# PCB_mezzanine_analog_template.net
KiCad netlist of a schematic drawn in Altium Designer
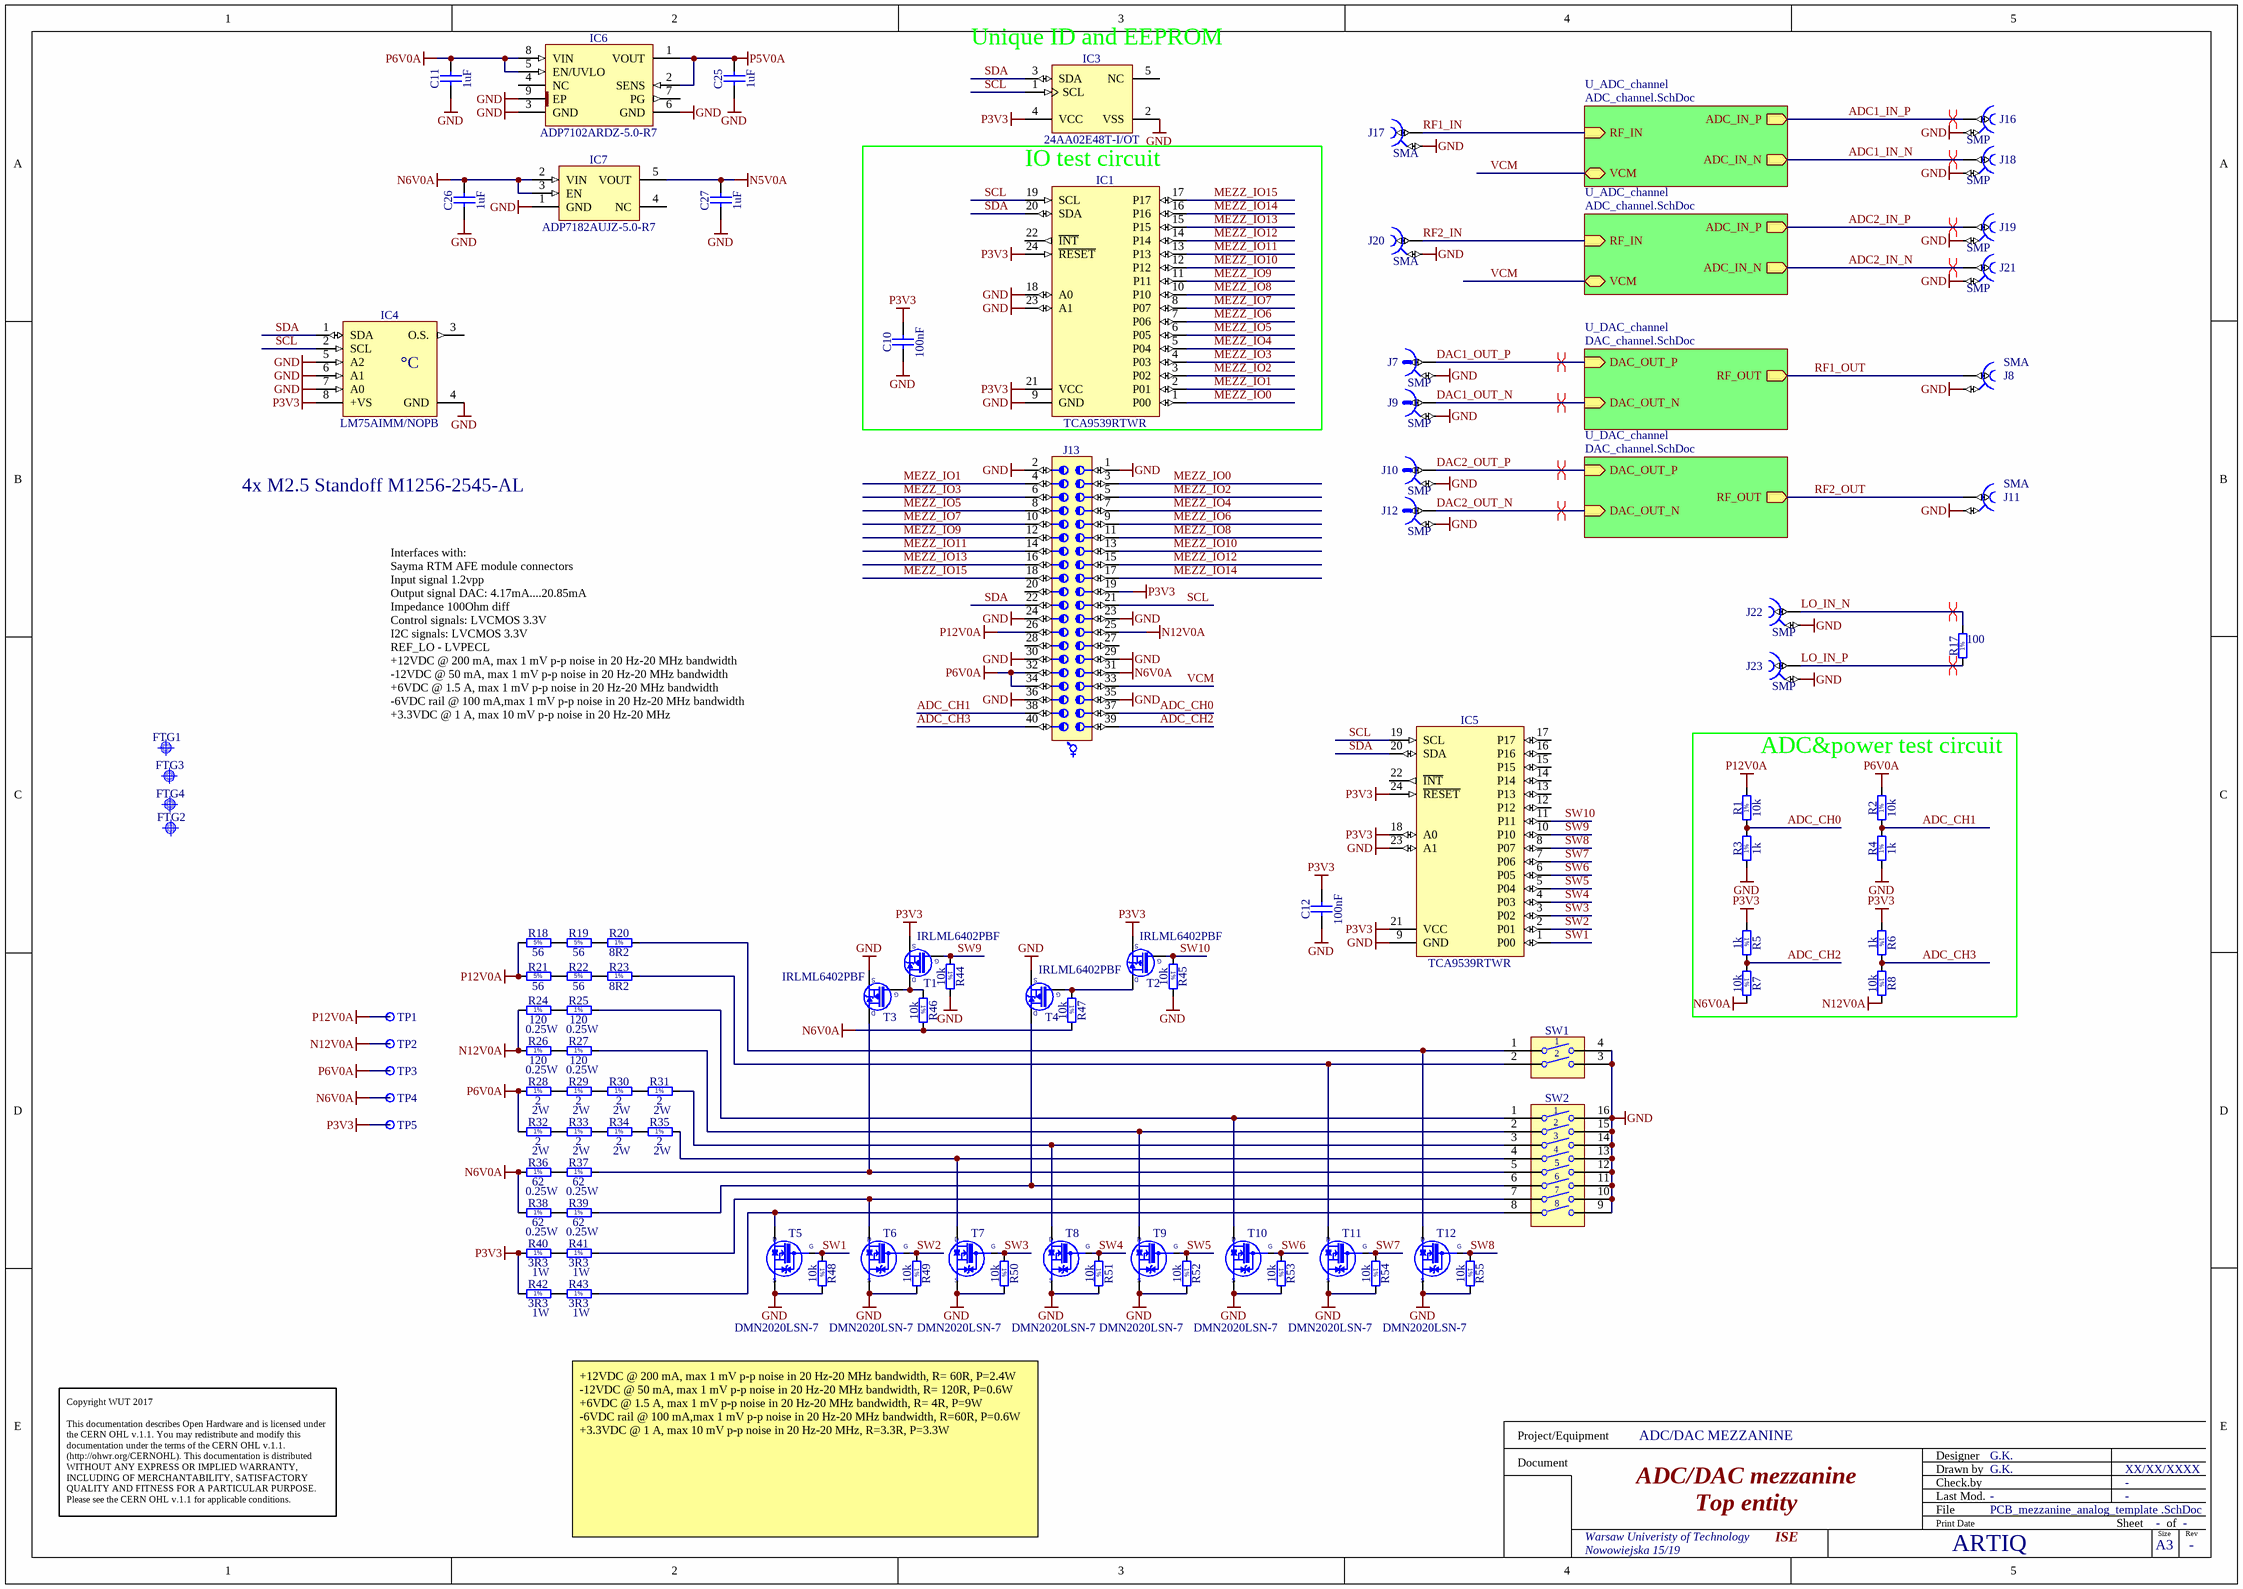
[diagram p0: PCB_mezzanine_analog_template .SchDoc]

(export (version "E")
  (design (tool "Eeschema 10.0.6"))
  (components
    (comp (ref "C10")
      (value "100nF")
      (footprint "CAPC1005X55N")
      (description "Non-polarised capacitor")
      (fields
        (field (name "PART NUMBER") "CC0402_100NF_16V_10%_X5R")
        (field (name "VOLTAGE") "16V")
        (field (name "AUTHOR") "CERN DEM JLC")
      )
      (libsource (lib "Capacitors") (part "Capacitor - non polarized"))
    )
    (comp (ref "C11")
      (value "1uF")
      (footprint "CAPC2012X140N")
      (description "Non-polarised capacitor")
      (fields
        (field (name "PART NUMBER") "CC0805_1UF_35V_20%_X7R")
        (field (name "VOLTAGE") "35V")
        (field (name "AUTHOR") "CERN DEM JLC")
      )
      (libsource (lib "Capacitors") (part "Capacitor - non polarized"))
    )
    (comp (ref "C12")
      (value "100nF")
      (footprint "CAPC1005X55N")
      (description "Non-polarised capacitor")
      (fields
        (field (name "PART NUMBER") "CC0402_100NF_16V_10%_X5R")
        (field (name "VOLTAGE") "16V")
        (field (name "AUTHOR") "CERN DEM JLC")
      )
      (libsource (lib "Capacitors") (part "Capacitor - non polarized"))
    )
    (comp (ref "C25")
      (value "1uF")
      (footprint "CAPC2012X140N")
      (description "Non-polarised capacitor")
      (fields
        (field (name "PART NUMBER") "CC0805_1UF_35V_20%_X7R")
        (field (name "VOLTAGE") "35V")
        (field (name "AUTHOR") "CERN DEM JLC")
      )
      (libsource (lib "Capacitors") (part "Capacitor - non polarized"))
    )
    (comp (ref "C26")
      (value "1uF")
      (footprint "CAPC2012X140N")
      (description "Non-polarised capacitor")
      (fields
        (field (name "PART NUMBER") "CC0805_1UF_35V_20%_X7R")
        (field (name "VOLTAGE") "35V")
        (field (name "AUTHOR") "CERN DEM JLC")
      )
      (libsource (lib "Capacitors") (part "Capacitor - non polarized"))
    )
    (comp (ref "C27")
      (value "1uF")
      (footprint "CAPC2012X140N")
      (description "Non-polarised capacitor")
      (fields
        (field (name "PART NUMBER") "CC0805_1UF_35V_20%_X7R")
        (field (name "VOLTAGE") "35V")
        (field (name "AUTHOR") "CERN DEM JLC")
      )
      (libsource (lib "Capacitors") (part "Capacitor - non polarized"))
    )
    (comp (ref "FTG1")
      (value "Use only in PCB")
      (footprint "FIDUCIAL_TOP_C100-200")
      (description "Fiducial Target")
      (fields (field (name "PART NUMBER") "FIDUCIAL_TARGET_C100-200") (field (name "AUTHOR") "CERN DEM JLC"))
      (libsource (lib "Eletro-mechanical") (part "Fiducial Target"))
    )
    (comp (ref "FTG2")
      (value "Use only in PCB")
      (footprint "FIDUCIAL_TOP_S100-200")
      (description "Fiducial Target")
      (fields (field (name "PART NUMBER") "FIDUCIAL_TARGET_S100-200") (field (name "AUTHOR") "CERN DEM JLC"))
      (libsource (lib "Eletro-mechanical") (part "Fiducial Target"))
    )
    (comp (ref "FTG3")
      (value "Use only in PCB")
      (footprint "FIDUCIAL_TOP_S100-200")
      (description "Fiducial Target")
      (fields (field (name "PART NUMBER") "FIDUCIAL_TARGET_S100-200") (field (name "AUTHOR") "CERN DEM JLC"))
      (libsource (lib "Eletro-mechanical") (part "Fiducial Target"))
    )
    (comp (ref "FTG4")
      (value "Use only in PCB")
      (footprint "FIDUCIAL_TOP_S200-400")
      (description "Fiducial Target")
      (fields (field (name "PART NUMBER") "FIDUCIAL_TARGET_S200-400") (field (name "AUTHOR") "CERN DEM JLC"))
      (libsource (lib "Eletro-mechanical") (part "Fiducial Target"))
    )
    (comp (ref "IC1")
      (value "TCA9539RTWR")
      (footprint "QFN50P400X400X80-25N-S255")
      (description "Low-Voltage 16-Bit I2C and SMBus I/O Expander")
      (fields (field (name "MANUFACTURER") "TEXAS INSTRUMENTS") (field (name "AUTHOR") "CERN DEM MR"))
      (libsource (lib "ICs And Semiconductors") (part "TCA9539RTWR"))
    )
    (comp (ref "IC3")
      (value "24AA02E48T-I/OT")
      (footprint "SOT95P280X145-5N")
      (description "1.7V-5.5V, 2K I2C Serial EEPROM With EUI-48 Node Identity")
      (fields (field (name "MANUFACTURER") "MICROCHIP TECHNOLOGY") (field (name "AUTHOR") "CERN DEM MR"))
      (libsource (lib "ICs And Semiconductors") (part "24AA02E48T-I/OT"))
    )
    (comp (ref "IC4")
      (value "LM75AIMM/NOPB")
      (footprint "SOP65P490X109-8N")
      (description "Digital Temperature Sensor and Thermal Watchdog with Two-Wire Interface")
      (fields (field (name "MANUFACTURER") "TEXAS INSTRUMENTS") (field (name "AUTHOR") "CERN DEM JLC"))
      (libsource (lib "ICs And Semiconductors") (part "LM75"))
    )
    (comp (ref "IC5")
      (value "TCA9539RTWR")
      (footprint "QFN50P400X400X80-25N-S255")
      (description "Low-Voltage 16-Bit I2C and SMBus I/O Expander")
      (fields (field (name "MANUFACTURER") "TEXAS INSTRUMENTS") (field (name "AUTHOR") "CERN DEM MR"))
      (libsource (lib "ICs And Semiconductors") (part "TCA9539RTWR"))
    )
    (comp (ref "IC6")
      (value "ADP7102ARDZ-5.0-R7")
      (footprint "SOIC127P600X175-9N-R241X309")
      (description "300 mA, Low Noise, CMOS LDO Linear Regulator")
      (fields (field (name "MANUFACTURER") "ANALOG DEVICES") (field (name "AUTHOR") "CERN DEM JLC"))
      (libsource (lib "ICs And Semiconductors") (part "ADP7102ARDZ-X.X-R7"))
    )
    (comp (ref "IC7")
      (value "ADP7182AUJZ-5.0-R7")
      (footprint "SOT95P280X90-5N")
      (description "–5V, 200 mA, Low Noise, Linear Regulator")
      (fields (field (name "MANUFACTURER") "ANALOG DEVICES") (field (name "AUTHOR") "CERN DEM JLC"))
      (libsource (lib "ICs And Semiconductors") (part "ADP7182AUJZ-X.X-R7"))
    )
    (comp (ref "J7")
      (value "SMP")
      (footprint "MOLEX_85305-0232")
      (fields
        (field (name "PART NUMBER") "MOLEX_85305-0232")
        (field (name "MANUFACTURER") "MOLEX")
        (field (name "MANUFACTURER PART NUMBER") "85305-0232")
        (field (name "AUTHOR") "CERN DEM JMW")
      )
      (libsource (lib "Connectors") (part "Coax_1Male_1Shield"))
    )
    (comp (ref "J8")
      (value "SMA")
      (footprint "TELEGARTNER_J01151A0451")
      (fields
        (field (name "PART NUMBER") "TELEGARTNER_J01151A0451")
        (field (name "MANUFACTURER") "TELEGARTNER")
        (field (name "MANUFACTURER PART NUMBER") "J01151A0451")
        (field (name "AUTHOR") "CERN DEM JLC")
      )
      (libsource (lib "") (part "Coax_1Female_1Shield_1"))
    )
    (comp (ref "J9")
      (value "SMP")
      (footprint "MOLEX_85305-0232")
      (fields
        (field (name "PART NUMBER") "MOLEX_85305-0232")
        (field (name "MANUFACTURER") "MOLEX")
        (field (name "MANUFACTURER PART NUMBER") "85305-0232")
        (field (name "AUTHOR") "CERN DEM JMW")
      )
      (libsource (lib "Connectors") (part "Coax_1Male_1Shield"))
    )
    (comp (ref "J10")
      (value "SMP")
      (footprint "MOLEX_85305-0232")
      (fields
        (field (name "PART NUMBER") "MOLEX_85305-0232")
        (field (name "MANUFACTURER") "MOLEX")
        (field (name "MANUFACTURER PART NUMBER") "85305-0232")
        (field (name "AUTHOR") "CERN DEM JMW")
      )
      (libsource (lib "Connectors") (part "Coax_1Male_1Shield"))
    )
    (comp (ref "J11")
      (value "SMA")
      (footprint "TELEGARTNER_J01151A0451")
      (fields
        (field (name "PART NUMBER") "TELEGARTNER_J01151A0451")
        (field (name "MANUFACTURER") "TELEGARTNER")
        (field (name "MANUFACTURER PART NUMBER") "J01151A0451")
        (field (name "AUTHOR") "CERN DEM JLC")
      )
      (libsource (lib "") (part "Coax_1Female_1Shield_1"))
    )
    (comp (ref "J12")
      (value "SMP")
      (footprint "MOLEX_85305-0232")
      (fields
        (field (name "PART NUMBER") "MOLEX_85305-0232")
        (field (name "MANUFACTURER") "MOLEX")
        (field (name "MANUFACTURER PART NUMBER") "85305-0232")
        (field (name "AUTHOR") "CERN DEM JMW")
      )
      (libsource (lib "Connectors") (part "Coax_1Male_1Shield"))
    )
    (comp (ref "J13")
      (value "~")
      (footprint "SAMTEC_LSS-120-02-L-DV-A")
      (fields
        (field (name "PART NUMBER") "SAMTEC_LSS-120-02-L-DV-A")
        (field (name "MANUFACTURER") "SAMTEC")
        (field (name "MANUFACTURER PART NUMBER") "LSS-120-02-L-DV-A")
        (field (name "AUTHOR") "CERN DEM JMW")
      )
      (libsource (lib "LIBRARY_SCH") (part "CON_SAMTEC_LSS-120-02-L-DV-A"))
    )
    (comp (ref "J16")
      (value "SMP")
      (footprint "AMPHENOL_SMP-MSLD-PCT-10")
      (fields
        (field (name "PART NUMBER") "AMPHENOL_SMP-MSLD-PCT-10")
        (field (name "MANUFACTURER") "AMPHENOL")
        (field (name "MANUFACTURER PART NUMBER") "SMP-MSLD-PCT-10")
        (field (name "AUTHOR") "CERN DEM JLC")
      )
      (libsource (lib "") (part "Coax_1Female_1Shield_1"))
    )
    (comp (ref "J17")
      (value "SMA")
      (footprint "TELEGARTNER_J01151A0921")
      (fields
        (field (name "PART NUMBER") "TELEGARTNER_J01151A0921")
        (field (name "MANUFACTURER") "TELEGARTNER")
        (field (name "MANUFACTURER PART NUMBER") "J01151A0921")
        (field (name "AUTHOR") "CERN DEM JLC")
      )
      (libsource (lib "Connectors") (part "Coax_1Female_1Shield"))
    )
    (comp (ref "J18")
      (value "SMP")
      (footprint "AMPHENOL_SMP-MSLD-PCT-10")
      (fields
        (field (name "PART NUMBER") "AMPHENOL_SMP-MSLD-PCT-10")
        (field (name "MANUFACTURER") "AMPHENOL")
        (field (name "MANUFACTURER PART NUMBER") "SMP-MSLD-PCT-10")
        (field (name "AUTHOR") "CERN DEM JLC")
      )
      (libsource (lib "") (part "Coax_1Female_1Shield_1"))
    )
    (comp (ref "J19")
      (value "SMP")
      (footprint "AMPHENOL_SMP-MSLD-PCT-10")
      (fields
        (field (name "PART NUMBER") "AMPHENOL_SMP-MSLD-PCT-10")
        (field (name "MANUFACTURER") "AMPHENOL")
        (field (name "MANUFACTURER PART NUMBER") "SMP-MSLD-PCT-10")
        (field (name "AUTHOR") "CERN DEM JLC")
      )
      (libsource (lib "") (part "Coax_1Female_1Shield_1"))
    )
    (comp (ref "J20")
      (value "SMA")
      (footprint "TELEGARTNER_J01151A0921")
      (fields
        (field (name "PART NUMBER") "TELEGARTNER_J01151A0921")
        (field (name "MANUFACTURER") "TELEGARTNER")
        (field (name "MANUFACTURER PART NUMBER") "J01151A0921")
        (field (name "AUTHOR") "CERN DEM JLC")
      )
      (libsource (lib "Connectors") (part "Coax_1Female_1Shield"))
    )
    (comp (ref "J21")
      (value "SMP")
      (footprint "AMPHENOL_SMP-MSLD-PCT-10")
      (fields
        (field (name "PART NUMBER") "AMPHENOL_SMP-MSLD-PCT-10")
        (field (name "MANUFACTURER") "AMPHENOL")
        (field (name "MANUFACTURER PART NUMBER") "SMP-MSLD-PCT-10")
        (field (name "AUTHOR") "CERN DEM JLC")
      )
      (libsource (lib "") (part "Coax_1Female_1Shield_1"))
    )
    (comp (ref "J22")
      (value "SMP")
      (footprint "AMPHENOL_SMP-MSLD-PCT-10")
      (fields
        (field (name "PART NUMBER") "AMPHENOL_SMP-MSLD-PCT-10")
        (field (name "MANUFACTURER") "AMPHENOL")
        (field (name "MANUFACTURER PART NUMBER") "SMP-MSLD-PCT-10")
        (field (name "AUTHOR") "CERN DEM JLC")
      )
      (libsource (lib "Connectors") (part "Coax_1Female_1Shield"))
    )
    (comp (ref "J23")
      (value "SMP")
      (footprint "AMPHENOL_SMP-MSLD-PCT-10")
      (fields
        (field (name "PART NUMBER") "AMPHENOL_SMP-MSLD-PCT-10")
        (field (name "MANUFACTURER") "AMPHENOL")
        (field (name "MANUFACTURER PART NUMBER") "SMP-MSLD-PCT-10")
        (field (name "AUTHOR") "CERN DEM JLC")
      )
      (libsource (lib "Connectors") (part "Coax_1Female_1Shield"))
    )
    (comp (ref "R1")
      (value "10k")
      (footprint "RESC1005X40N")
      (description "Resistor - 1%")
      (fields
        (field (name "PART NUMBER") "R0402_10K_1%_0.0625W_100PPM")
        (field (name "POWER") "0.0625W")
        (field (name "AUTHOR") "CERN DEM JLC")
      )
      (libsource (lib "Resistors") (part "Resistor - 1%"))
    )
    (comp (ref "R2")
      (value "10k")
      (footprint "RESC1005X40N")
      (description "Resistor - 1%")
      (fields
        (field (name "PART NUMBER") "R0402_10K_1%_0.0625W_100PPM")
        (field (name "POWER") "0.0625W")
        (field (name "AUTHOR") "CERN DEM JLC")
      )
      (libsource (lib "Resistors") (part "Resistor - 1%"))
    )
    (comp (ref "R3")
      (value "1k")
      (footprint "RESC1005X40N")
      (description "Resistor - 1%")
      (fields
        (field (name "PART NUMBER") "R0402_1K_1%_0.0625W_100PPM")
        (field (name "POWER") "0.0625W")
        (field (name "AUTHOR") "CERN DEM JLC")
      )
      (libsource (lib "Resistors") (part "Resistor - 1%"))
    )
    (comp (ref "R4")
      (value "1k")
      (footprint "RESC1005X40N")
      (description "Resistor - 1%")
      (fields
        (field (name "PART NUMBER") "R0402_1K_1%_0.0625W_100PPM")
        (field (name "POWER") "0.0625W")
        (field (name "AUTHOR") "CERN DEM JLC")
      )
      (libsource (lib "Resistors") (part "Resistor - 1%"))
    )
    (comp (ref "R5")
      (value "1k")
      (footprint "RESC1005X40N")
      (description "Resistor - 1%")
      (fields
        (field (name "PART NUMBER") "R0402_1K_1%_0.0625W_100PPM")
        (field (name "POWER") "0.0625W")
        (field (name "AUTHOR") "CERN DEM JLC")
      )
      (libsource (lib "Resistors") (part "Resistor - 1%"))
    )
    (comp (ref "R6")
      (value "1k")
      (footprint "RESC1005X40N")
      (description "Resistor - 1%")
      (fields
        (field (name "PART NUMBER") "R0402_1K_1%_0.0625W_100PPM")
        (field (name "POWER") "0.0625W")
        (field (name "AUTHOR") "CERN DEM JLC")
      )
      (libsource (lib "Resistors") (part "Resistor - 1%"))
    )
    (comp (ref "R7")
      (value "10k")
      (footprint "RESC1005X40N")
      (description "Resistor - 1%")
      (fields
        (field (name "PART NUMBER") "R0402_10K_1%_0.0625W_100PPM")
        (field (name "POWER") "0.0625W")
        (field (name "AUTHOR") "CERN DEM JLC")
      )
      (libsource (lib "Resistors") (part "Resistor - 1%"))
    )
    (comp (ref "R8")
      (value "10k")
      (footprint "RESC1005X40N")
      (description "Resistor - 1%")
      (fields
        (field (name "PART NUMBER") "R0402_10K_1%_0.0625W_100PPM")
        (field (name "POWER") "0.0625W")
        (field (name "AUTHOR") "CERN DEM JLC")
      )
      (libsource (lib "Resistors") (part "Resistor - 1%"))
    )
    (comp (ref "R17")
      (value "100")
      (footprint "RESC1005X40N")
      (description "Resistor - 1%")
      (fields
        (field (name "PART NUMBER") "R0402_100R_1%_0.0625W_100PPM")
        (field (name "POWER") "0.0625W")
        (field (name "AUTHOR") "CERN DEM JLC")
      )
      (libsource (lib "Resistors") (part "Resistor - 1%"))
    )
    (comp (ref "R18")
      (value "56")
      (footprint "RESC6331X70N")
      (description "Resistor - 5%")
      (fields
        (field (name "PART NUMBER") "R2512_56R_5%_1W_200PPM")
        (field (name "POWER") "1W")
        (field (name "AUTHOR") "CERN DEM JLC")
      )
      (libsource (lib "Resistors") (part "Resistor - 5%"))
    )
    (comp (ref "R19")
      (value "56")
      (footprint "RESC6331X70N")
      (description "Resistor - 5%")
      (fields
        (field (name "PART NUMBER") "R2512_56R_5%_1W_200PPM")
        (field (name "POWER") "1W")
        (field (name "AUTHOR") "CERN DEM JLC")
      )
      (libsource (lib "Resistors") (part "Resistor - 5%"))
    )
    (comp (ref "R20")
      (value "8R2")
      (footprint "RESC3216X65N")
      (description "Resistor - 1%")
      (fields
        (field (name "PART NUMBER") "R1206_8R2_1%_0.25W_200PPM")
        (field (name "POWER") "0.25W")
        (field (name "AUTHOR") "CERN DEM JLC")
      )
      (libsource (lib "Resistors") (part "Resistor - 1%"))
    )
    (comp (ref "R21")
      (value "56")
      (footprint "RESC6331X70N")
      (description "Resistor - 5%")
      (fields
        (field (name "PART NUMBER") "R2512_56R_5%_1W_200PPM")
        (field (name "POWER") "1W")
        (field (name "AUTHOR") "CERN DEM JLC")
      )
      (libsource (lib "Resistors") (part "Resistor - 5%"))
    )
    (comp (ref "R22")
      (value "56")
      (footprint "RESC6331X70N")
      (description "Resistor - 5%")
      (fields
        (field (name "PART NUMBER") "R2512_56R_5%_1W_200PPM")
        (field (name "POWER") "1W")
        (field (name "AUTHOR") "CERN DEM JLC")
      )
      (libsource (lib "Resistors") (part "Resistor - 5%"))
    )
    (comp (ref "R23")
      (value "8R2")
      (footprint "RESC3216X65N")
      (description "Resistor - 1%")
      (fields
        (field (name "PART NUMBER") "R1206_8R2_1%_0.25W_200PPM")
        (field (name "POWER") "0.25W")
        (field (name "AUTHOR") "CERN DEM JLC")
      )
      (libsource (lib "Resistors") (part "Resistor - 1%"))
    )
    (comp (ref "R24")
      (value "120")
      (footprint "RESC3216X65N")
      (description "Resistor - 1%")
      (fields
        (field (name "PART NUMBER") "R1206_120R_1%_0.25W_100PPM")
        (field (name "POWER") "0.25W")
        (field (name "TOLERANCE") "±1%")
        (field (name "AUTHOR") "CERN DEM JLC")
      )
      (libsource (lib "Resistors") (part "Resistor - 1%"))
    )
    (comp (ref "R25")
      (value "120")
      (footprint "RESC3216X65N")
      (description "Resistor - 1%")
      (fields
        (field (name "PART NUMBER") "R1206_120R_1%_0.25W_100PPM")
        (field (name "POWER") "0.25W")
        (field (name "TOLERANCE") "±1%")
        (field (name "AUTHOR") "CERN DEM JLC")
      )
      (libsource (lib "Resistors") (part "Resistor - 1%"))
    )
    (comp (ref "R26")
      (value "120")
      (footprint "RESC3216X65N")
      (description "Resistor - 1%")
      (fields
        (field (name "PART NUMBER") "R1206_120R_1%_0.25W_100PPM")
        (field (name "POWER") "0.25W")
        (field (name "TOLERANCE") "±1%")
        (field (name "AUTHOR") "CERN DEM JLC")
      )
      (libsource (lib "Resistors") (part "Resistor - 1%"))
    )
    (comp (ref "R27")
      (value "120")
      (footprint "RESC3216X65N")
      (description "Resistor - 1%")
      (fields
        (field (name "PART NUMBER") "R1206_120R_1%_0.25W_100PPM")
        (field (name "POWER") "0.25W")
        (field (name "TOLERANCE") "±1%")
        (field (name "AUTHOR") "CERN DEM JLC")
      )
      (libsource (lib "Resistors") (part "Resistor - 1%"))
    )
    (comp (ref "R28")
      (value "2")
      (footprint "RESM11670X449N")
      (description "Resistor - 1%")
      (fields
        (field (name "PART NUMBER") "R4527_2R_1%_2W_50PPM")
        (field (name "POWER") "2W")
        (field (name "TOLERANCE") "±1%")
        (field (name "AUTHOR") "CERN DEM JLC")
      )
      (libsource (lib "Resistors") (part "Resistor - 1%"))
    )
    (comp (ref "R29")
      (value "2")
      (footprint "RESM11670X449N")
      (description "Resistor - 1%")
      (fields
        (field (name "PART NUMBER") "R4527_2R_1%_2W_50PPM")
        (field (name "POWER") "2W")
        (field (name "TOLERANCE") "±1%")
        (field (name "AUTHOR") "CERN DEM JLC")
      )
      (libsource (lib "Resistors") (part "Resistor - 1%"))
    )
    (comp (ref "R30")
      (value "2")
      (footprint "RESM11670X449N")
      (description "Resistor - 1%")
      (fields
        (field (name "PART NUMBER") "R4527_2R_1%_2W_50PPM")
        (field (name "POWER") "2W")
        (field (name "TOLERANCE") "±1%")
        (field (name "AUTHOR") "CERN DEM JLC")
      )
      (libsource (lib "Resistors") (part "Resistor - 1%"))
    )
    (comp (ref "R31")
      (value "2")
      (footprint "RESM11670X449N")
      (description "Resistor - 1%")
      (fields
        (field (name "PART NUMBER") "R4527_2R_1%_2W_50PPM")
        (field (name "POWER") "2W")
        (field (name "TOLERANCE") "±1%")
        (field (name "AUTHOR") "CERN DEM JLC")
      )
      (libsource (lib "Resistors") (part "Resistor - 1%"))
    )
    (comp (ref "R32")
      (value "2")
      (footprint "RESM11670X449N")
      (description "Resistor - 1%")
      (fields
        (field (name "PART NUMBER") "R4527_2R_1%_2W_50PPM")
        (field (name "POWER") "2W")
        (field (name "TOLERANCE") "±1%")
        (field (name "AUTHOR") "CERN DEM JLC")
      )
      (libsource (lib "Resistors") (part "Resistor - 1%"))
    )
    (comp (ref "R33")
      (value "2")
      (footprint "RESM11670X449N")
      (description "Resistor - 1%")
      (fields
        (field (name "PART NUMBER") "R4527_2R_1%_2W_50PPM")
        (field (name "POWER") "2W")
        (field (name "TOLERANCE") "±1%")
        (field (name "AUTHOR") "CERN DEM JLC")
      )
      (libsource (lib "Resistors") (part "Resistor - 1%"))
    )
    (comp (ref "R34")
      (value "2")
      (footprint "RESM11670X449N")
      (description "Resistor - 1%")
      (fields
        (field (name "PART NUMBER") "R4527_2R_1%_2W_50PPM")
        (field (name "POWER") "2W")
        (field (name "TOLERANCE") "±1%")
        (field (name "AUTHOR") "CERN DEM JLC")
      )
      (libsource (lib "Resistors") (part "Resistor - 1%"))
    )
    (comp (ref "R35")
      (value "2")
      (footprint "RESM11670X449N")
      (description "Resistor - 1%")
      (fields
        (field (name "PART NUMBER") "R4527_2R_1%_2W_50PPM")
        (field (name "POWER") "2W")
        (field (name "TOLERANCE") "±1%")
        (field (name "AUTHOR") "CERN DEM JLC")
      )
      (libsource (lib "Resistors") (part "Resistor - 1%"))
    )
    (comp (ref "R36")
      (value "62")
      (footprint "RESC3216X65N")
      (description "Resistor - 1%")
      (fields
        (field (name "PART NUMBER") "R1206_62R_1%_0.25W_100PPM")
        (field (name "POWER") "0.25W")
        (field (name "TOLERANCE") "±1%")
        (field (name "AUTHOR") "CERN DEM JLC")
      )
      (libsource (lib "Resistors") (part "Resistor - 1%"))
    )
    (comp (ref "R37")
      (value "62")
      (footprint "RESC3216X65N")
      (description "Resistor - 1%")
      (fields
        (field (name "PART NUMBER") "R1206_62R_1%_0.25W_100PPM")
        (field (name "POWER") "0.25W")
        (field (name "TOLERANCE") "±1%")
        (field (name "AUTHOR") "CERN DEM JLC")
      )
      (libsource (lib "Resistors") (part "Resistor - 1%"))
    )
    (comp (ref "R38")
      (value "62")
      (footprint "RESC3216X65N")
      (description "Resistor - 1%")
      (fields
        (field (name "PART NUMBER") "R1206_62R_1%_0.25W_100PPM")
        (field (name "POWER") "0.25W")
        (field (name "TOLERANCE") "±1%")
        (field (name "AUTHOR") "CERN DEM JLC")
      )
      (libsource (lib "Resistors") (part "Resistor - 1%"))
    )
    (comp (ref "R39")
      (value "62")
      (footprint "RESC3216X65N")
      (description "Resistor - 1%")
      (fields
        (field (name "PART NUMBER") "R1206_62R_1%_0.25W_100PPM")
        (field (name "POWER") "0.25W")
        (field (name "TOLERANCE") "±1%")
        (field (name "AUTHOR") "CERN DEM JLC")
      )
      (libsource (lib "Resistors") (part "Resistor - 1%"))
    )
    (comp (ref "R40")
      (value "3R3")
      (footprint "RESC6331X70N")
      (description "Resistor - 1%")
      (fields
        (field (name "PART NUMBER") "R2512_3R3_1%_1W_200PPM")
        (field (name "POWER") "1W")
        (field (name "TOLERANCE") "±1%")
        (field (name "AUTHOR") "CERN DEM JLC")
      )
      (libsource (lib "Resistors") (part "Resistor - 1%"))
    )
    (comp (ref "R41")
      (value "3R3")
      (footprint "RESC6331X70N")
      (description "Resistor - 1%")
      (fields
        (field (name "PART NUMBER") "R2512_3R3_1%_1W_200PPM")
        (field (name "POWER") "1W")
        (field (name "TOLERANCE") "±1%")
        (field (name "AUTHOR") "CERN DEM JLC")
      )
      (libsource (lib "Resistors") (part "Resistor - 1%"))
    )
    (comp (ref "R42")
      (value "3R3")
      (footprint "RESC6331X70N")
      (description "Resistor - 1%")
      (fields
        (field (name "PART NUMBER") "R2512_3R3_1%_1W_200PPM")
        (field (name "POWER") "1W")
        (field (name "TOLERANCE") "±1%")
        (field (name "AUTHOR") "CERN DEM JLC")
      )
      (libsource (lib "Resistors") (part "Resistor - 1%"))
    )
    (comp (ref "R43")
      (value "3R3")
      (footprint "RESC6331X70N")
      (description "Resistor - 1%")
      (fields
        (field (name "PART NUMBER") "R2512_3R3_1%_1W_200PPM")
        (field (name "POWER") "1W")
        (field (name "TOLERANCE") "±1%")
        (field (name "AUTHOR") "CERN DEM JLC")
      )
      (libsource (lib "Resistors") (part "Resistor - 1%"))
    )
    (comp (ref "R44")
      (value "10k")
      (footprint "RESC1005X40N")
      (description "Resistor - 1%")
      (fields
        (field (name "PART NUMBER") "R0402_10K_1%_0.0625W_100PPM")
        (field (name "POWER") "0.0625W")
        (field (name "AUTHOR") "CERN DEM JLC")
      )
      (libsource (lib "Resistors") (part "Resistor - 1%"))
    )
    (comp (ref "R45")
      (value "10k")
      (footprint "RESC1005X40N")
      (description "Resistor - 1%")
      (fields
        (field (name "PART NUMBER") "R0402_10K_1%_0.0625W_100PPM")
        (field (name "POWER") "0.0625W")
        (field (name "AUTHOR") "CERN DEM JLC")
      )
      (libsource (lib "Resistors") (part "Resistor - 1%"))
    )
    (comp (ref "R46")
      (value "10k")
      (footprint "RESC1005X40N")
      (description "Resistor - 1%")
      (fields
        (field (name "PART NUMBER") "R0402_10K_1%_0.0625W_100PPM")
        (field (name "POWER") "0.0625W")
        (field (name "AUTHOR") "CERN DEM JLC")
      )
      (libsource (lib "Resistors") (part "Resistor - 1%"))
    )
    (comp (ref "R47")
      (value "10k")
      (footprint "RESC1005X40N")
      (description "Resistor - 1%")
      (fields
        (field (name "PART NUMBER") "R0402_10K_1%_0.0625W_100PPM")
        (field (name "POWER") "0.0625W")
        (field (name "AUTHOR") "CERN DEM JLC")
      )
      (libsource (lib "Resistors") (part "Resistor - 1%"))
    )
    (comp (ref "R48")
      (value "10k")
      (footprint "RESC1005X40N")
      (description "Resistor - 1%")
      (fields
        (field (name "PART NUMBER") "R0402_10K_1%_0.0625W_100PPM")
        (field (name "POWER") "0.0625W")
        (field (name "AUTHOR") "CERN DEM JLC")
      )
      (libsource (lib "Resistors") (part "Resistor - 1%"))
    )
    (comp (ref "R49")
      (value "10k")
      (footprint "RESC1005X40N")
      (description "Resistor - 1%")
      (fields
        (field (name "PART NUMBER") "R0402_10K_1%_0.0625W_100PPM")
        (field (name "POWER") "0.0625W")
        (field (name "AUTHOR") "CERN DEM JLC")
      )
      (libsource (lib "Resistors") (part "Resistor - 1%"))
    )
    (comp (ref "R50")
      (value "10k")
      (footprint "RESC1005X40N")
      (description "Resistor - 1%")
      (fields
        (field (name "PART NUMBER") "R0402_10K_1%_0.0625W_100PPM")
        (field (name "POWER") "0.0625W")
        (field (name "AUTHOR") "CERN DEM JLC")
      )
      (libsource (lib "Resistors") (part "Resistor - 1%"))
    )
    (comp (ref "R51")
      (value "10k")
      (footprint "RESC1005X40N")
      (description "Resistor - 1%")
      (fields
        (field (name "PART NUMBER") "R0402_10K_1%_0.0625W_100PPM")
        (field (name "POWER") "0.0625W")
        (field (name "AUTHOR") "CERN DEM JLC")
      )
      (libsource (lib "Resistors") (part "Resistor - 1%"))
    )
    (comp (ref "R52")
      (value "10k")
      (footprint "RESC1005X40N")
      (description "Resistor - 1%")
      (fields
        (field (name "PART NUMBER") "R0402_10K_1%_0.0625W_100PPM")
        (field (name "POWER") "0.0625W")
        (field (name "AUTHOR") "CERN DEM JLC")
      )
      (libsource (lib "Resistors") (part "Resistor - 1%"))
    )
    (comp (ref "R53")
      (value "10k")
      (footprint "RESC1005X40N")
      (description "Resistor - 1%")
      (fields
        (field (name "PART NUMBER") "R0402_10K_1%_0.0625W_100PPM")
        (field (name "POWER") "0.0625W")
        (field (name "AUTHOR") "CERN DEM JLC")
      )
      (libsource (lib "Resistors") (part "Resistor - 1%"))
    )
    (comp (ref "R54")
      (value "10k")
      (footprint "RESC1005X40N")
      (description "Resistor - 1%")
      (fields
        (field (name "PART NUMBER") "R0402_10K_1%_0.0625W_100PPM")
        (field (name "POWER") "0.0625W")
        (field (name "AUTHOR") "CERN DEM JLC")
      )
      (libsource (lib "Resistors") (part "Resistor - 1%"))
    )
    (comp (ref "R55")
      (value "10k")
      (footprint "RESC1005X40N")
      (description "Resistor - 1%")
      (fields
        (field (name "PART NUMBER") "R0402_10K_1%_0.0625W_100PPM")
        (field (name "POWER") "0.0625W")
        (field (name "AUTHOR") "CERN DEM JLC")
      )
      (libsource (lib "Resistors") (part "Resistor - 1%"))
    )
    (comp (ref "SW1")
      (value "Switch")
      (footprint "SW_OMRON_A6S-2102-H")
      (description "2 Ways SPST DIP Switch")
      (fields
        (field (name "PART NUMBER") "SW_OMRON_A6S-2102-H")
        (field (name "MANUFACTURER") "OMRON")
        (field (name "AUTHOR") "CERN DEM JMW")
      )
      (libsource (lib "Eletro-mechanical") (part "SW 2x SPST DIP Switch"))
    )
    (comp (ref "SW2")
      (value "Switch")
      (footprint "SW_OMRON_A6S-8102-H")
      (description "8 Ways SPST DIP Switch")
      (fields
        (field (name "PART NUMBER") "SW_OMRON_A6S-8102-H")
        (field (name "MANUFACTURER") "OMRON")
        (field (name "AUTHOR") "CERN DEM JMW")
      )
      (libsource (lib "Eletro-mechanical") (part "SW 8x SPST DIP Switch"))
    )
    (comp (ref "T1")
      (value "IRLML6402PBF")
      (footprint "SOT95P237X112-3N")
      (description "P-CHANNEL MOSFET WITH ZENER DIODE")
      (fields (field (name "MANUFACTURER") "INTERNATIONAL RECTIFIER") (field (name "AUTHOR") "CERN DEM JLC"))
      (libsource (lib "ICs And Semiconductors") (part "P-MOSFET-DZ 1G 2S 3D"))
    )
    (comp (ref "T2")
      (value "IRLML6402PBF")
      (footprint "SOT95P237X112-3N")
      (description "P-CHANNEL MOSFET WITH ZENER DIODE")
      (fields (field (name "MANUFACTURER") "INTERNATIONAL RECTIFIER") (field (name "AUTHOR") "CERN DEM JLC"))
      (libsource (lib "ICs And Semiconductors") (part "P-MOSFET-DZ 1G 2S 3D"))
    )
    (comp (ref "T3")
      (value "IRLML6402PBF")
      (footprint "SOT95P237X112-3N")
      (description "P-CHANNEL MOSFET WITH ZENER DIODE")
      (fields (field (name "MANUFACTURER") "INTERNATIONAL RECTIFIER") (field (name "AUTHOR") "CERN DEM JLC"))
      (libsource (lib "ICs And Semiconductors") (part "P-MOSFET-DZ 1G 2S 3D"))
    )
    (comp (ref "T4")
      (value "IRLML6402PBF")
      (footprint "SOT95P237X112-3N")
      (description "P-CHANNEL MOSFET WITH ZENER DIODE")
      (fields (field (name "MANUFACTURER") "INTERNATIONAL RECTIFIER") (field (name "AUTHOR") "CERN DEM JLC"))
      (libsource (lib "ICs And Semiconductors") (part "P-MOSFET-DZ 1G 2S 3D"))
    )
    (comp (ref "T5")
      (value "DMN2020LSN-7")
      (footprint "SOT95P285X140-3N")
      (description "20V, 6.9A, N-Channel Enhancement Mode MOSFET")
      (fields (field (name "MANUFACTURER") "DIODES INCORPORATED") (field (name "AUTHOR") "CERN DEM JLC"))
      (libsource (lib "ICs And Semiconductors") (part "DMN2020LSN-7"))
    )
    (comp (ref "T6")
      (value "DMN2020LSN-7")
      (footprint "SOT95P285X140-3N")
      (description "20V, 6.9A, N-Channel Enhancement Mode MOSFET")
      (fields (field (name "MANUFACTURER") "DIODES INCORPORATED") (field (name "AUTHOR") "CERN DEM JLC"))
      (libsource (lib "ICs And Semiconductors") (part "DMN2020LSN-7"))
    )
    (comp (ref "T7")
      (value "DMN2020LSN-7")
      (footprint "SOT95P285X140-3N")
      (description "20V, 6.9A, N-Channel Enhancement Mode MOSFET")
      (fields (field (name "MANUFACTURER") "DIODES INCORPORATED") (field (name "AUTHOR") "CERN DEM JLC"))
      (libsource (lib "ICs And Semiconductors") (part "DMN2020LSN-7"))
    )
    (comp (ref "T8")
      (value "DMN2020LSN-7")
      (footprint "SOT95P285X140-3N")
      (description "20V, 6.9A, N-Channel Enhancement Mode MOSFET")
      (fields (field (name "MANUFACTURER") "DIODES INCORPORATED") (field (name "AUTHOR") "CERN DEM JLC"))
      (libsource (lib "ICs And Semiconductors") (part "DMN2020LSN-7"))
    )
    (comp (ref "T9")
      (value "DMN2020LSN-7")
      (footprint "SOT95P285X140-3N")
      (description "20V, 6.9A, N-Channel Enhancement Mode MOSFET")
      (fields (field (name "MANUFACTURER") "DIODES INCORPORATED") (field (name "AUTHOR") "CERN DEM JLC"))
      (libsource (lib "ICs And Semiconductors") (part "DMN2020LSN-7"))
    )
    (comp (ref "T10")
      (value "DMN2020LSN-7")
      (footprint "SOT95P285X140-3N")
      (description "20V, 6.9A, N-Channel Enhancement Mode MOSFET")
      (fields (field (name "MANUFACTURER") "DIODES INCORPORATED") (field (name "AUTHOR") "CERN DEM JLC"))
      (libsource (lib "ICs And Semiconductors") (part "DMN2020LSN-7"))
    )
    (comp (ref "T11")
      (value "DMN2020LSN-7")
      (footprint "SOT95P285X140-3N")
      (description "20V, 6.9A, N-Channel Enhancement Mode MOSFET")
      (fields (field (name "MANUFACTURER") "DIODES INCORPORATED") (field (name "AUTHOR") "CERN DEM JLC"))
      (libsource (lib "ICs And Semiconductors") (part "DMN2020LSN-7"))
    )
    (comp (ref "T12")
      (value "DMN2020LSN-7")
      (footprint "SOT95P285X140-3N")
      (description "20V, 6.9A, N-Channel Enhancement Mode MOSFET")
      (fields (field (name "MANUFACTURER") "DIODES INCORPORATED") (field (name "AUTHOR") "CERN DEM JLC"))
      (libsource (lib "ICs And Semiconductors") (part "DMN2020LSN-7"))
    )
    (comp (ref "TP1")
      (value "Test Point")
      (footprint "TPS127")
      (fields (field (name "PART NUMBER") "SMD_PAD_1.27X1.27MM") (field (name "AUTHOR") "CERN DEM JLC"))
      (libsource (lib "Eletro-mechanical") (part "Test Point"))
    )
    (comp (ref "TP2")
      (value "Test Point")
      (footprint "TPS127")
      (fields (field (name "PART NUMBER") "SMD_PAD_1.27X1.27MM") (field (name "AUTHOR") "CERN DEM JLC"))
      (libsource (lib "Eletro-mechanical") (part "Test Point"))
    )
    (comp (ref "TP3")
      (value "Test Point")
      (footprint "TPS127")
      (fields (field (name "PART NUMBER") "SMD_PAD_1.27X1.27MM") (field (name "AUTHOR") "CERN DEM JLC"))
      (libsource (lib "Eletro-mechanical") (part "Test Point"))
    )
    (comp (ref "TP4")
      (value "Test Point")
      (footprint "TPS127")
      (fields (field (name "PART NUMBER") "SMD_PAD_1.27X1.27MM") (field (name "AUTHOR") "CERN DEM JLC"))
      (libsource (lib "Eletro-mechanical") (part "Test Point"))
    )
    (comp (ref "TP5")
      (value "Test Point")
      (footprint "TPS127")
      (fields (field (name "PART NUMBER") "SMD_PAD_1.27X1.27MM") (field (name "AUTHOR") "CERN DEM JLC"))
      (libsource (lib "Eletro-mechanical") (part "Test Point"))
    )
  )
  (nets
    (net (code "1") (name "/ADC1_IN_N") (class "Default")
      (node (ref "J18") (pin "1") (pinfunction "1_1") (pintype "bidirectional"))
    )
    (net (code "2") (name "/ADC1_IN_P") (class "Default")
      (node (ref "J16") (pin "1") (pinfunction "1_1") (pintype "bidirectional"))
    )
    (net (code "3") (name "/ADC2_IN_N") (class "Default")
      (node (ref "J21") (pin "1") (pinfunction "1_1") (pintype "bidirectional"))
    )
    (net (code "4") (name "/ADC2_IN_P") (class "Default")
      (node (ref "J19") (pin "1") (pinfunction "1_1") (pintype "bidirectional"))
    )
    (net (code "5") (name "/ADC_CH0") (class "Default")
      (node (ref "J13") (pin "37") (pinfunction "37_37") (pintype "bidirectional"))
      (node (ref "R1") (pin "1") (pinfunction "1_1") (pintype "passive"))
      (node (ref "R3") (pin "2") (pinfunction "2_2") (pintype "passive"))
    )
    (net (code "6") (name "/ADC_CH1") (class "Default")
      (node (ref "J13") (pin "38") (pinfunction "38_38") (pintype "bidirectional"))
      (node (ref "R2") (pin "1") (pinfunction "1_1") (pintype "passive"))
      (node (ref "R4") (pin "2") (pinfunction "2_2") (pintype "passive"))
    )
    (net (code "7") (name "/ADC_CH2") (class "Default")
      (node (ref "J13") (pin "39") (pinfunction "39_39") (pintype "bidirectional"))
      (node (ref "R5") (pin "2") (pinfunction "2_2") (pintype "passive"))
      (node (ref "R7") (pin "1") (pinfunction "1_1") (pintype "passive"))
    )
    (net (code "8") (name "/ADC_CH3") (class "Default")
      (node (ref "J13") (pin "40") (pinfunction "40_40") (pintype "bidirectional"))
      (node (ref "R6") (pin "2") (pinfunction "2_2") (pintype "passive"))
      (node (ref "R8") (pin "1") (pinfunction "1_1") (pintype "passive"))
    )
    (net (code "9") (name "/DAC1_OUT_N") (class "Default")
      (node (ref "J9") (pin "1") (pinfunction "1_1") (pintype "bidirectional"))
    )
    (net (code "10") (name "/DAC1_OUT_P") (class "Default")
      (node (ref "J7") (pin "1") (pinfunction "1_1") (pintype "bidirectional"))
    )
    (net (code "11") (name "/DAC2_OUT_N") (class "Default")
      (node (ref "J12") (pin "1") (pinfunction "1_1") (pintype "bidirectional"))
    )
    (net (code "12") (name "/DAC2_OUT_P") (class "Default")
      (node (ref "J10") (pin "1") (pinfunction "1_1") (pintype "bidirectional"))
    )
    (net (code "13") (name "/LO_IN_N") (class "Default")
      (node (ref "J22") (pin "1") (pinfunction "1_1") (pintype "bidirectional"))
      (node (ref "R17") (pin "2") (pinfunction "2_2") (pintype "passive"))
    )
    (net (code "14") (name "/LO_IN_P") (class "Default")
      (node (ref "J23") (pin "1") (pinfunction "1_1") (pintype "bidirectional"))
      (node (ref "R17") (pin "1") (pinfunction "1_1") (pintype "passive"))
    )
    (net (code "15") (name "/MEZZ_IO0") (class "Default")
      (node (ref "IC1") (pin "1") (pinfunction "P00_1") (pintype "bidirectional"))
      (node (ref "J13") (pin "3") (pinfunction "3_3") (pintype "bidirectional"))
    )
    (net (code "16") (name "/MEZZ_IO1") (class "Default")
      (node (ref "IC1") (pin "2") (pinfunction "P01_2") (pintype "bidirectional"))
      (node (ref "J13") (pin "4") (pinfunction "4_4") (pintype "bidirectional"))
    )
    (net (code "17") (name "/MEZZ_IO2") (class "Default")
      (node (ref "IC1") (pin "3") (pinfunction "P02_3") (pintype "bidirectional"))
      (node (ref "J13") (pin "5") (pinfunction "5_5") (pintype "bidirectional"))
    )
    (net (code "18") (name "/MEZZ_IO3") (class "Default")
      (node (ref "IC1") (pin "4") (pinfunction "P03_4") (pintype "bidirectional"))
      (node (ref "J13") (pin "6") (pinfunction "6_6") (pintype "bidirectional"))
    )
    (net (code "19") (name "/MEZZ_IO4") (class "Default")
      (node (ref "IC1") (pin "5") (pinfunction "P04_5") (pintype "bidirectional"))
      (node (ref "J13") (pin "7") (pinfunction "7_7") (pintype "bidirectional"))
    )
    (net (code "20") (name "/MEZZ_IO5") (class "Default")
      (node (ref "IC1") (pin "6") (pinfunction "P05_6") (pintype "bidirectional"))
      (node (ref "J13") (pin "8") (pinfunction "8_8") (pintype "bidirectional"))
    )
    (net (code "21") (name "/MEZZ_IO6") (class "Default")
      (node (ref "IC1") (pin "7") (pinfunction "P06_7") (pintype "bidirectional"))
      (node (ref "J13") (pin "9") (pinfunction "9_9") (pintype "bidirectional"))
    )
    (net (code "22") (name "/MEZZ_IO7") (class "Default")
      (node (ref "IC1") (pin "8") (pinfunction "P07_8") (pintype "bidirectional"))
      (node (ref "J13") (pin "10") (pinfunction "10_10") (pintype "bidirectional"))
    )
    (net (code "23") (name "/MEZZ_IO8") (class "Default")
      (node (ref "IC1") (pin "10") (pinfunction "P10_10") (pintype "bidirectional"))
      (node (ref "J13") (pin "11") (pinfunction "11_11") (pintype "bidirectional"))
    )
    (net (code "24") (name "/MEZZ_IO9") (class "Default")
      (node (ref "IC1") (pin "11") (pinfunction "P11_11") (pintype "bidirectional"))
      (node (ref "J13") (pin "12") (pinfunction "12_12") (pintype "bidirectional"))
    )
    (net (code "25") (name "/MEZZ_IO10") (class "Default")
      (node (ref "IC1") (pin "12") (pinfunction "P12_12") (pintype "bidirectional"))
      (node (ref "J13") (pin "13") (pinfunction "13_13") (pintype "bidirectional"))
    )
    (net (code "26") (name "/MEZZ_IO11") (class "Default")
      (node (ref "IC1") (pin "13") (pinfunction "P13_13") (pintype "bidirectional"))
      (node (ref "J13") (pin "14") (pinfunction "14_14") (pintype "bidirectional"))
    )
    (net (code "27") (name "/MEZZ_IO12") (class "Default")
      (node (ref "IC1") (pin "14") (pinfunction "P14_14") (pintype "bidirectional"))
      (node (ref "J13") (pin "15") (pinfunction "15_15") (pintype "bidirectional"))
    )
    (net (code "28") (name "/MEZZ_IO13") (class "Default")
      (node (ref "IC1") (pin "15") (pinfunction "P15_15") (pintype "bidirectional"))
      (node (ref "J13") (pin "16") (pinfunction "16_16") (pintype "bidirectional"))
    )
    (net (code "29") (name "/MEZZ_IO14") (class "Default")
      (node (ref "IC1") (pin "16") (pinfunction "P16_16") (pintype "bidirectional"))
      (node (ref "J13") (pin "17") (pinfunction "17_17") (pintype "bidirectional"))
    )
    (net (code "30") (name "/MEZZ_IO15") (class "Default")
      (node (ref "IC1") (pin "17") (pinfunction "P17_17") (pintype "bidirectional"))
      (node (ref "J13") (pin "18") (pinfunction "18_18") (pintype "bidirectional"))
    )
    (net (code "31") (name "/RF1_IN") (class "Default")
      (node (ref "J17") (pin "1") (pinfunction "1_1") (pintype "bidirectional"))
    )
    (net (code "32") (name "/RF1_OUT") (class "Default")
      (node (ref "J8") (pin "1") (pinfunction "1_1") (pintype "bidirectional"))
    )
    (net (code "33") (name "/RF2_IN") (class "Default")
      (node (ref "J20") (pin "1") (pinfunction "1_1") (pintype "bidirectional"))
    )
    (net (code "34") (name "/RF2_OUT") (class "Default")
      (node (ref "J11") (pin "1") (pinfunction "1_1") (pintype "bidirectional"))
    )
    (net (code "35") (name "/SCL") (class "Default")
      (node (ref "IC1") (pin "19") (pinfunction "SCL_19") (pintype "input"))
      (node (ref "IC3") (pin "1") (pinfunction "SCL_1") (pintype "input"))
      (node (ref "IC4") (pin "2") (pinfunction "SCL_2") (pintype "input"))
      (node (ref "IC5") (pin "19") (pinfunction "SCL_19") (pintype "input"))
      (node (ref "J13") (pin "21") (pinfunction "21_21") (pintype "bidirectional"))
    )
    (net (code "36") (name "/SDA") (class "Default")
      (node (ref "IC1") (pin "20") (pinfunction "SDA_20") (pintype "bidirectional"))
      (node (ref "IC3") (pin "3") (pinfunction "SDA_3") (pintype "bidirectional"))
      (node (ref "IC4") (pin "1") (pinfunction "SDA_1") (pintype "bidirectional"))
      (node (ref "IC5") (pin "20") (pinfunction "SDA_20") (pintype "bidirectional"))
      (node (ref "J13") (pin "22") (pinfunction "22_22") (pintype "bidirectional"))
    )
    (net (code "37") (name "/SW1") (class "Default")
      (node (ref "IC5") (pin "1") (pinfunction "P00_1") (pintype "bidirectional"))
      (node (ref "R48") (pin "1") (pinfunction "1_1") (pintype "passive"))
      (node (ref "T5") (pin "1") (pinfunction "G_1") (pintype "passive"))
    )
    (net (code "38") (name "/SW2") (class "Default")
      (node (ref "IC5") (pin "2") (pinfunction "P01_2") (pintype "bidirectional"))
      (node (ref "R49") (pin "1") (pinfunction "1_1") (pintype "passive"))
      (node (ref "T6") (pin "1") (pinfunction "G_1") (pintype "passive"))
    )
    (net (code "39") (name "/SW3") (class "Default")
      (node (ref "IC5") (pin "3") (pinfunction "P02_3") (pintype "bidirectional"))
      (node (ref "R50") (pin "1") (pinfunction "1_1") (pintype "passive"))
      (node (ref "T7") (pin "1") (pinfunction "G_1") (pintype "passive"))
    )
    (net (code "40") (name "/SW4") (class "Default")
      (node (ref "IC5") (pin "4") (pinfunction "P03_4") (pintype "bidirectional"))
      (node (ref "R51") (pin "1") (pinfunction "1_1") (pintype "passive"))
      (node (ref "T8") (pin "1") (pinfunction "G_1") (pintype "passive"))
    )
    (net (code "41") (name "/SW5") (class "Default")
      (node (ref "IC5") (pin "5") (pinfunction "P04_5") (pintype "bidirectional"))
      (node (ref "R52") (pin "1") (pinfunction "1_1") (pintype "passive"))
      (node (ref "T9") (pin "1") (pinfunction "G_1") (pintype "passive"))
    )
    (net (code "42") (name "/SW6") (class "Default")
      (node (ref "IC5") (pin "6") (pinfunction "P05_6") (pintype "bidirectional"))
      (node (ref "R53") (pin "1") (pinfunction "1_1") (pintype "passive"))
      (node (ref "T10") (pin "1") (pinfunction "G_1") (pintype "passive"))
    )
    (net (code "43") (name "/SW7") (class "Default")
      (node (ref "IC5") (pin "7") (pinfunction "P06_7") (pintype "bidirectional"))
      (node (ref "R54") (pin "1") (pinfunction "1_1") (pintype "passive"))
      (node (ref "T11") (pin "1") (pinfunction "G_1") (pintype "passive"))
    )
    (net (code "44") (name "/SW8") (class "Default")
      (node (ref "IC5") (pin "8") (pinfunction "P07_8") (pintype "bidirectional"))
      (node (ref "R55") (pin "1") (pinfunction "1_1") (pintype "passive"))
      (node (ref "T12") (pin "1") (pinfunction "G_1") (pintype "passive"))
    )
    (net (code "45") (name "/SW9") (class "Default")
      (node (ref "IC5") (pin "10") (pinfunction "P10_10") (pintype "bidirectional"))
      (node (ref "R44") (pin "1") (pinfunction "1_1") (pintype "passive"))
      (node (ref "T1") (pin "1") (pinfunction "G_1") (pintype "passive"))
    )
    (net (code "46") (name "/SW10") (class "Default")
      (node (ref "IC5") (pin "11") (pinfunction "P11_11") (pintype "bidirectional"))
      (node (ref "R45") (pin "1") (pinfunction "1_1") (pintype "passive"))
      (node (ref "T2") (pin "1") (pinfunction "G_1") (pintype "passive"))
    )
    (net (code "47") (name "/VCM") (class "Default")
      (node (ref "J13") (pin "33") (pinfunction "33_33") (pintype "bidirectional"))
    )
    (net (code "48") (name "GND") (class "Default")
      (node (ref "C10") (pin "1") (pinfunction "1_1") (pintype "passive"))
      (node (ref "C11") (pin "1") (pinfunction "1_1") (pintype "passive"))
      (node (ref "C12") (pin "1") (pinfunction "1_1") (pintype "passive"))
      (node (ref "C25") (pin "1") (pinfunction "1_1") (pintype "passive"))
      (node (ref "C26") (pin "1") (pinfunction "1_1") (pintype "passive"))
      (node (ref "C27") (pin "1") (pinfunction "1_1") (pintype "passive"))
      (node (ref "IC1") (pin "18") (pinfunction "A0_18") (pintype "bidirectional"))
      (node (ref "IC1") (pin "23") (pinfunction "A1_23") (pintype "bidirectional"))
      (node (ref "IC1") (pin "9") (pinfunction "GND_9") (pintype "power_in"))
      (node (ref "IC3") (pin "2") (pinfunction "VSS_2") (pintype "power_in"))
      (node (ref "IC4") (pin "4") (pinfunction "GND_4") (pintype "power_in"))
      (node (ref "IC4") (pin "5") (pinfunction "A2_5") (pintype "input"))
      (node (ref "IC4") (pin "6") (pinfunction "A1_6") (pintype "input"))
      (node (ref "IC4") (pin "7") (pinfunction "A0_7") (pintype "input"))
      (node (ref "IC5") (pin "23") (pinfunction "A1_23") (pintype "bidirectional"))
      (node (ref "IC5") (pin "9") (pinfunction "GND_9") (pintype "power_in"))
      (node (ref "IC6") (pin "3") (pinfunction "GND_3") (pintype "power_in"))
      (node (ref "IC6") (pin "6") (pinfunction "GND_6") (pintype "power_in"))
      (node (ref "IC6") (pin "9") (pinfunction "EP_9") (pintype "power_in"))
      (node (ref "IC7") (pin "1") (pinfunction "GND_1") (pintype "power_in"))
      (node (ref "J10") (pin "2") (pinfunction "2_2") (pintype "bidirectional"))
      (node (ref "J11") (pin "2") (pinfunction "2_2") (pintype "bidirectional"))
      (node (ref "J12") (pin "2") (pinfunction "2_2") (pintype "bidirectional"))
      (node (ref "J13") (pin "1") (pinfunction "1_1") (pintype "bidirectional"))
      (node (ref "J13") (pin "2") (pinfunction "2_2") (pintype "bidirectional"))
      (node (ref "J13") (pin "23") (pinfunction "23_23") (pintype "bidirectional"))
      (node (ref "J13") (pin "24") (pinfunction "24_24") (pintype "bidirectional"))
      (node (ref "J13") (pin "29") (pinfunction "29_29") (pintype "bidirectional"))
      (node (ref "J13") (pin "30") (pinfunction "30_30") (pintype "bidirectional"))
      (node (ref "J13") (pin "35") (pinfunction "35_35") (pintype "bidirectional"))
      (node (ref "J13") (pin "36") (pinfunction "36_36") (pintype "bidirectional"))
      (node (ref "J16") (pin "2") (pinfunction "2_2") (pintype "bidirectional"))
      (node (ref "J17") (pin "2") (pinfunction "2_2") (pintype "bidirectional"))
      (node (ref "J18") (pin "2") (pinfunction "2_2") (pintype "bidirectional"))
      (node (ref "J19") (pin "2") (pinfunction "2_2") (pintype "bidirectional"))
      (node (ref "J20") (pin "2") (pinfunction "2_2") (pintype "bidirectional"))
      (node (ref "J21") (pin "2") (pinfunction "2_2") (pintype "bidirectional"))
      (node (ref "J22") (pin "2") (pinfunction "2_2") (pintype "bidirectional"))
      (node (ref "J23") (pin "2") (pinfunction "2_2") (pintype "bidirectional"))
      (node (ref "J7") (pin "2") (pinfunction "2_2") (pintype "bidirectional"))
      (node (ref "J8") (pin "2") (pinfunction "2_2") (pintype "bidirectional"))
      (node (ref "J9") (pin "2") (pinfunction "2_2") (pintype "bidirectional"))
      (node (ref "R3") (pin "1") (pinfunction "1_1") (pintype "passive"))
      (node (ref "R4") (pin "1") (pinfunction "1_1") (pintype "passive"))
      (node (ref "R44") (pin "2") (pinfunction "2_2") (pintype "passive"))
      (node (ref "R45") (pin "2") (pinfunction "2_2") (pintype "passive"))
      (node (ref "R48") (pin "2") (pinfunction "2_2") (pintype "passive"))
      (node (ref "R49") (pin "2") (pinfunction "2_2") (pintype "passive"))
      (node (ref "R50") (pin "2") (pinfunction "2_2") (pintype "passive"))
      (node (ref "R51") (pin "2") (pinfunction "2_2") (pintype "passive"))
      (node (ref "R52") (pin "2") (pinfunction "2_2") (pintype "passive"))
      (node (ref "R53") (pin "2") (pinfunction "2_2") (pintype "passive"))
      (node (ref "R54") (pin "2") (pinfunction "2_2") (pintype "passive"))
      (node (ref "R55") (pin "2") (pinfunction "2_2") (pintype "passive"))
      (node (ref "SW1") (pin "3") (pinfunction "3_3") (pintype "passive"))
      (node (ref "SW1") (pin "4") (pinfunction "4_4") (pintype "passive"))
      (node (ref "SW2") (pin "10") (pinfunction "10_10") (pintype "passive"))
      (node (ref "SW2") (pin "11") (pinfunction "11_11") (pintype "passive"))
      (node (ref "SW2") (pin "12") (pinfunction "12_12") (pintype "passive"))
      (node (ref "SW2") (pin "13") (pinfunction "13_13") (pintype "passive"))
      (node (ref "SW2") (pin "14") (pinfunction "14_14") (pintype "passive"))
      (node (ref "SW2") (pin "15") (pinfunction "15_15") (pintype "passive"))
      (node (ref "SW2") (pin "16") (pinfunction "16_16") (pintype "passive"))
      (node (ref "SW2") (pin "9") (pinfunction "9_9") (pintype "passive"))
      (node (ref "T10") (pin "2") (pinfunction "S_2") (pintype "passive"))
      (node (ref "T11") (pin "2") (pinfunction "S_2") (pintype "passive"))
      (node (ref "T12") (pin "2") (pinfunction "S_2") (pintype "passive"))
      (node (ref "T3") (pin "2") (pinfunction "S_2") (pintype "passive"))
      (node (ref "T4") (pin "2") (pinfunction "S_2") (pintype "passive"))
      (node (ref "T5") (pin "2") (pinfunction "S_2") (pintype "passive"))
      (node (ref "T6") (pin "2") (pinfunction "S_2") (pintype "passive"))
      (node (ref "T7") (pin "2") (pinfunction "S_2") (pintype "passive"))
      (node (ref "T8") (pin "2") (pinfunction "S_2") (pintype "passive"))
      (node (ref "T9") (pin "2") (pinfunction "S_2") (pintype "passive"))
    )
    (net (code "49") (name "N5V0A") (class "Default")
      (node (ref "C27") (pin "2") (pinfunction "2_2") (pintype "passive"))
      (node (ref "IC7") (pin "5") (pinfunction "VOUT_5") (pintype "power_in"))
    )
    (net (code "50") (name "N6V0A") (class "Default")
      (node (ref "C26") (pin "2") (pinfunction "2_2") (pintype "passive"))
      (node (ref "IC7") (pin "2") (pinfunction "VIN_2") (pintype "input"))
      (node (ref "IC7") (pin "3") (pinfunction "EN_3") (pintype "input"))
      (node (ref "J13") (pin "31") (pinfunction "31_31") (pintype "bidirectional"))
      (node (ref "R36") (pin "1") (pinfunction "1_1") (pintype "passive"))
      (node (ref "R38") (pin "1") (pinfunction "1_1") (pintype "passive"))
      (node (ref "R46") (pin "2") (pinfunction "2_2") (pintype "passive"))
      (node (ref "R47") (pin "2") (pinfunction "2_2") (pintype "passive"))
      (node (ref "R7") (pin "2") (pinfunction "2_2") (pintype "passive"))
      (node (ref "TP4") (pin "1") (pinfunction "1_1") (pintype "bidirectional"))
    )
    (net (code "51") (name "N12V0A") (class "Default")
      (node (ref "J13") (pin "25") (pinfunction "25_25") (pintype "bidirectional"))
      (node (ref "R24") (pin "1") (pinfunction "1_1") (pintype "passive"))
      (node (ref "R26") (pin "1") (pinfunction "1_1") (pintype "passive"))
      (node (ref "R8") (pin "2") (pinfunction "2_2") (pintype "passive"))
      (node (ref "TP2") (pin "1") (pinfunction "1_1") (pintype "bidirectional"))
    )
    (net (code "52") (name "Net-(R18-Pad2)") (class "Default")
      (node (ref "R18") (pin "2") (pinfunction "2_2") (pintype "passive"))
      (node (ref "R19") (pin "1") (pinfunction "1_1") (pintype "passive"))
    )
    (net (code "53") (name "Net-(R19-Pad2)") (class "Default")
      (node (ref "R19") (pin "2") (pinfunction "2_2") (pintype "passive"))
      (node (ref "R20") (pin "1") (pinfunction "1_1") (pintype "passive"))
    )
    (net (code "54") (name "Net-(R21-Pad2)") (class "Default")
      (node (ref "R21") (pin "2") (pinfunction "2_2") (pintype "passive"))
      (node (ref "R22") (pin "1") (pinfunction "1_1") (pintype "passive"))
    )
    (net (code "55") (name "Net-(R22-Pad2)") (class "Default")
      (node (ref "R22") (pin "2") (pinfunction "2_2") (pintype "passive"))
      (node (ref "R23") (pin "1") (pinfunction "1_1") (pintype "passive"))
    )
    (net (code "56") (name "Net-(R24-Pad2)") (class "Default")
      (node (ref "R24") (pin "2") (pinfunction "2_2") (pintype "passive"))
      (node (ref "R25") (pin "1") (pinfunction "1_1") (pintype "passive"))
    )
    (net (code "57") (name "Net-(R26-Pad2)") (class "Default")
      (node (ref "R26") (pin "2") (pinfunction "2_2") (pintype "passive"))
      (node (ref "R27") (pin "1") (pinfunction "1_1") (pintype "passive"))
    )
    (net (code "58") (name "Net-(R28-Pad2)") (class "Default")
      (node (ref "R28") (pin "2") (pinfunction "2_2") (pintype "passive"))
      (node (ref "R29") (pin "1") (pinfunction "1_1") (pintype "passive"))
    )
    (net (code "59") (name "Net-(R29-Pad2)") (class "Default")
      (node (ref "R29") (pin "2") (pinfunction "2_2") (pintype "passive"))
      (node (ref "R30") (pin "1") (pinfunction "1_1") (pintype "passive"))
    )
    (net (code "60") (name "Net-(R30-Pad2)") (class "Default")
      (node (ref "R30") (pin "2") (pinfunction "2_2") (pintype "passive"))
      (node (ref "R31") (pin "1") (pinfunction "1_1") (pintype "passive"))
    )
    (net (code "61") (name "Net-(R32-Pad2)") (class "Default")
      (node (ref "R32") (pin "2") (pinfunction "2_2") (pintype "passive"))
      (node (ref "R33") (pin "1") (pinfunction "1_1") (pintype "passive"))
    )
    (net (code "62") (name "Net-(R33-Pad2)") (class "Default")
      (node (ref "R33") (pin "2") (pinfunction "2_2") (pintype "passive"))
      (node (ref "R34") (pin "1") (pinfunction "1_1") (pintype "passive"))
    )
    (net (code "63") (name "Net-(R34-Pad2)") (class "Default")
      (node (ref "R34") (pin "2") (pinfunction "2_2") (pintype "passive"))
      (node (ref "R35") (pin "1") (pinfunction "1_1") (pintype "passive"))
    )
    (net (code "64") (name "Net-(R36-Pad2)") (class "Default")
      (node (ref "R36") (pin "2") (pinfunction "2_2") (pintype "passive"))
      (node (ref "R37") (pin "1") (pinfunction "1_1") (pintype "passive"))
    )
    (net (code "65") (name "Net-(R38-Pad2)") (class "Default")
      (node (ref "R38") (pin "2") (pinfunction "2_2") (pintype "passive"))
      (node (ref "R39") (pin "1") (pinfunction "1_1") (pintype "passive"))
    )
    (net (code "66") (name "Net-(R40-Pad2)") (class "Default")
      (node (ref "R40") (pin "2") (pinfunction "2_2") (pintype "passive"))
      (node (ref "R41") (pin "1") (pinfunction "1_1") (pintype "passive"))
    )
    (net (code "67") (name "Net-(R42-Pad2)") (class "Default")
      (node (ref "R42") (pin "2") (pinfunction "2_2") (pintype "passive"))
      (node (ref "R43") (pin "1") (pinfunction "1_1") (pintype "passive"))
    )
    (net (code "68") (name "Net-(T1-D)") (class "Default")
      (node (ref "R46") (pin "1") (pinfunction "1_1") (pintype "passive"))
      (node (ref "T1") (pin "3") (pinfunction "D_3") (pintype "passive"))
      (node (ref "T3") (pin "1") (pinfunction "G_1") (pintype "passive"))
    )
    (net (code "69") (name "Net-(T2-D)") (class "Default")
      (node (ref "R47") (pin "1") (pinfunction "1_1") (pintype "passive"))
      (node (ref "T2") (pin "3") (pinfunction "D_3") (pintype "passive"))
      (node (ref "T4") (pin "1") (pinfunction "G_1") (pintype "passive"))
    )
    (net (code "70") (name "Net-(T3-D)") (class "Default")
      (node (ref "R37") (pin "2") (pinfunction "2_2") (pintype "passive"))
      (node (ref "SW2") (pin "5") (pinfunction "5_5") (pintype "passive"))
      (node (ref "T3") (pin "3") (pinfunction "D_3") (pintype "passive"))
    )
    (net (code "71") (name "Net-(T4-D)") (class "Default")
      (node (ref "R39") (pin "2") (pinfunction "2_2") (pintype "passive"))
      (node (ref "SW2") (pin "6") (pinfunction "6_6") (pintype "passive"))
      (node (ref "T4") (pin "3") (pinfunction "D_3") (pintype "passive"))
    )
    (net (code "72") (name "Net-(T5-D)") (class "Default")
      (node (ref "R43") (pin "2") (pinfunction "2_2") (pintype "passive"))
      (node (ref "SW2") (pin "8") (pinfunction "8_8") (pintype "passive"))
      (node (ref "T5") (pin "3") (pinfunction "D_3") (pintype "passive"))
    )
    (net (code "73") (name "Net-(T6-D)") (class "Default")
      (node (ref "R41") (pin "2") (pinfunction "2_2") (pintype "passive"))
      (node (ref "SW2") (pin "7") (pinfunction "7_7") (pintype "passive"))
      (node (ref "T6") (pin "3") (pinfunction "D_3") (pintype "passive"))
    )
    (net (code "74") (name "Net-(T7-D)") (class "Default")
      (node (ref "R35") (pin "2") (pinfunction "2_2") (pintype "passive"))
      (node (ref "SW2") (pin "4") (pinfunction "4_4") (pintype "passive"))
      (node (ref "T7") (pin "3") (pinfunction "D_3") (pintype "passive"))
    )
    (net (code "75") (name "Net-(T8-D)") (class "Default")
      (node (ref "R31") (pin "2") (pinfunction "2_2") (pintype "passive"))
      (node (ref "SW2") (pin "3") (pinfunction "3_3") (pintype "passive"))
      (node (ref "T8") (pin "3") (pinfunction "D_3") (pintype "passive"))
    )
    (net (code "76") (name "Net-(T9-D)") (class "Default")
      (node (ref "R27") (pin "2") (pinfunction "2_2") (pintype "passive"))
      (node (ref "SW2") (pin "2") (pinfunction "2_2") (pintype "passive"))
      (node (ref "T9") (pin "3") (pinfunction "D_3") (pintype "passive"))
    )
    (net (code "77") (name "Net-(T10-D)") (class "Default")
      (node (ref "R25") (pin "2") (pinfunction "2_2") (pintype "passive"))
      (node (ref "SW2") (pin "1") (pinfunction "1_1") (pintype "passive"))
      (node (ref "T10") (pin "3") (pinfunction "D_3") (pintype "passive"))
    )
    (net (code "78") (name "Net-(T11-D)") (class "Default")
      (node (ref "R23") (pin "2") (pinfunction "2_2") (pintype "passive"))
      (node (ref "SW1") (pin "2") (pinfunction "2_2") (pintype "passive"))
      (node (ref "T11") (pin "3") (pinfunction "D_3") (pintype "passive"))
    )
    (net (code "79") (name "Net-(T12-D)") (class "Default")
      (node (ref "R20") (pin "2") (pinfunction "2_2") (pintype "passive"))
      (node (ref "SW1") (pin "1") (pinfunction "1_1") (pintype "passive"))
      (node (ref "T12") (pin "3") (pinfunction "D_3") (pintype "passive"))
    )
    (net (code "80") (name "P3V3") (class "Default")
      (node (ref "C10") (pin "2") (pinfunction "2_2") (pintype "passive"))
      (node (ref "C12") (pin "2") (pinfunction "2_2") (pintype "passive"))
      (node (ref "IC1") (pin "21") (pinfunction "VCC_21") (pintype "power_in"))
      (node (ref "IC1") (pin "24") (pinfunction "~{RESET}_24") (pintype "input"))
      (node (ref "IC3") (pin "4") (pinfunction "VCC_4") (pintype "power_in"))
      (node (ref "IC4") (pin "8") (pinfunction "+VS_8") (pintype "power_in"))
      (node (ref "IC5") (pin "18") (pinfunction "A0_18") (pintype "bidirectional"))
      (node (ref "IC5") (pin "21") (pinfunction "VCC_21") (pintype "power_in"))
      (node (ref "IC5") (pin "24") (pinfunction "~{RESET}_24") (pintype "input"))
      (node (ref "J13") (pin "19") (pinfunction "19_19") (pintype "bidirectional"))
      (node (ref "R40") (pin "1") (pinfunction "1_1") (pintype "passive"))
      (node (ref "R42") (pin "1") (pinfunction "1_1") (pintype "passive"))
      (node (ref "R5") (pin "1") (pinfunction "1_1") (pintype "passive"))
      (node (ref "R6") (pin "1") (pinfunction "1_1") (pintype "passive"))
      (node (ref "T1") (pin "2") (pinfunction "S_2") (pintype "passive"))
      (node (ref "T2") (pin "2") (pinfunction "S_2") (pintype "passive"))
      (node (ref "TP5") (pin "1") (pinfunction "1_1") (pintype "bidirectional"))
    )
    (net (code "81") (name "P5V0A") (class "Default")
      (node (ref "C25") (pin "2") (pinfunction "2_2") (pintype "passive"))
      (node (ref "IC6") (pin "1") (pinfunction "VOUT_1") (pintype "power_in"))
      (node (ref "IC6") (pin "2") (pinfunction "SENS_2") (pintype "input"))
    )
    (net (code "82") (name "P6V0A") (class "Default")
      (node (ref "C11") (pin "2") (pinfunction "2_2") (pintype "passive"))
      (node (ref "IC6") (pin "5") (pinfunction "EN/UVLO_5") (pintype "input"))
      (node (ref "IC6") (pin "8") (pinfunction "VIN_8") (pintype "input"))
      (node (ref "J13") (pin "32") (pinfunction "32_32") (pintype "bidirectional"))
      (node (ref "J13") (pin "34") (pinfunction "34_34") (pintype "bidirectional"))
      (node (ref "R2") (pin "2") (pinfunction "2_2") (pintype "passive"))
      (node (ref "R28") (pin "1") (pinfunction "1_1") (pintype "passive"))
      (node (ref "R32") (pin "1") (pinfunction "1_1") (pintype "passive"))
      (node (ref "TP3") (pin "1") (pinfunction "1_1") (pintype "bidirectional"))
    )
    (net (code "83") (name "P12V0A") (class "Default")
      (node (ref "J13") (pin "26") (pinfunction "26_26") (pintype "bidirectional"))
      (node (ref "R1") (pin "2") (pinfunction "2_2") (pintype "passive"))
      (node (ref "R18") (pin "1") (pinfunction "1_1") (pintype "passive"))
      (node (ref "R21") (pin "1") (pinfunction "1_1") (pintype "passive"))
      (node (ref "TP1") (pin "1") (pinfunction "1_1") (pintype "bidirectional"))
    )
    (net (code "84") (name "unconnected-(IC1-~{INT}-Pad22)") (class "Default")
      (node (ref "IC1") (pin "22") (pinfunction "~{INT}_22") (pintype "output"))
    )
    (net (code "85") (name "unconnected-(IC3-NC-Pad5)") (class "Default")
      (node (ref "IC3") (pin "5") (pinfunction "NC_5") (pintype "passive"))
    )
    (net (code "86") (name "unconnected-(IC4-O.S.-Pad3)") (class "Default")
      (node (ref "IC4") (pin "3") (pinfunction "O.S._3") (pintype "output"))
    )
    (net (code "87") (name "unconnected-(IC5-P12-Pad12)") (class "Default")
      (node (ref "IC5") (pin "12") (pinfunction "P12_12") (pintype "bidirectional"))
    )
    (net (code "88") (name "unconnected-(IC5-P13-Pad13)") (class "Default")
      (node (ref "IC5") (pin "13") (pinfunction "P13_13") (pintype "bidirectional"))
    )
    (net (code "89") (name "unconnected-(IC5-P14-Pad14)") (class "Default")
      (node (ref "IC5") (pin "14") (pinfunction "P14_14") (pintype "bidirectional"))
    )
    (net (code "90") (name "unconnected-(IC5-P15-Pad15)") (class "Default")
      (node (ref "IC5") (pin "15") (pinfunction "P15_15") (pintype "bidirectional"))
    )
    (net (code "91") (name "unconnected-(IC5-P16-Pad16)") (class "Default")
      (node (ref "IC5") (pin "16") (pinfunction "P16_16") (pintype "bidirectional"))
    )
    (net (code "92") (name "unconnected-(IC5-P17-Pad17)") (class "Default")
      (node (ref "IC5") (pin "17") (pinfunction "P17_17") (pintype "bidirectional"))
    )
    (net (code "93") (name "unconnected-(IC5-~{INT}-Pad22)") (class "Default")
      (node (ref "IC5") (pin "22") (pinfunction "~{INT}_22") (pintype "output"))
    )
    (net (code "94") (name "unconnected-(IC6-NC-Pad4)") (class "Default")
      (node (ref "IC6") (pin "4") (pinfunction "NC_4") (pintype "passive"))
    )
    (net (code "95") (name "unconnected-(IC6-PG-Pad7)") (class "Default")
      (node (ref "IC6") (pin "7") (pinfunction "PG_7") (pintype "output"))
    )
    (net (code "96") (name "unconnected-(IC7-NC-Pad4)") (class "Default")
      (node (ref "IC7") (pin "4") (pinfunction "NC_4") (pintype "passive"))
    )
    (net (code "97") (name "unconnected-(J13-Pad20)") (class "Default")
      (node (ref "J13") (pin "20") (pinfunction "20_20") (pintype "bidirectional"))
    )
    (net (code "98") (name "unconnected-(J13-Pad27)") (class "Default")
      (node (ref "J13") (pin "27") (pinfunction "27_27") (pintype "bidirectional"))
    )
    (net (code "99") (name "unconnected-(J13-Pad28)") (class "Default")
      (node (ref "J13") (pin "28") (pinfunction "28_28") (pintype "bidirectional"))
    )
  )
)
